# 04_VOLTAGE_CONVERTER.net
KiCad netlist of a schematic drawn in Altium Designer
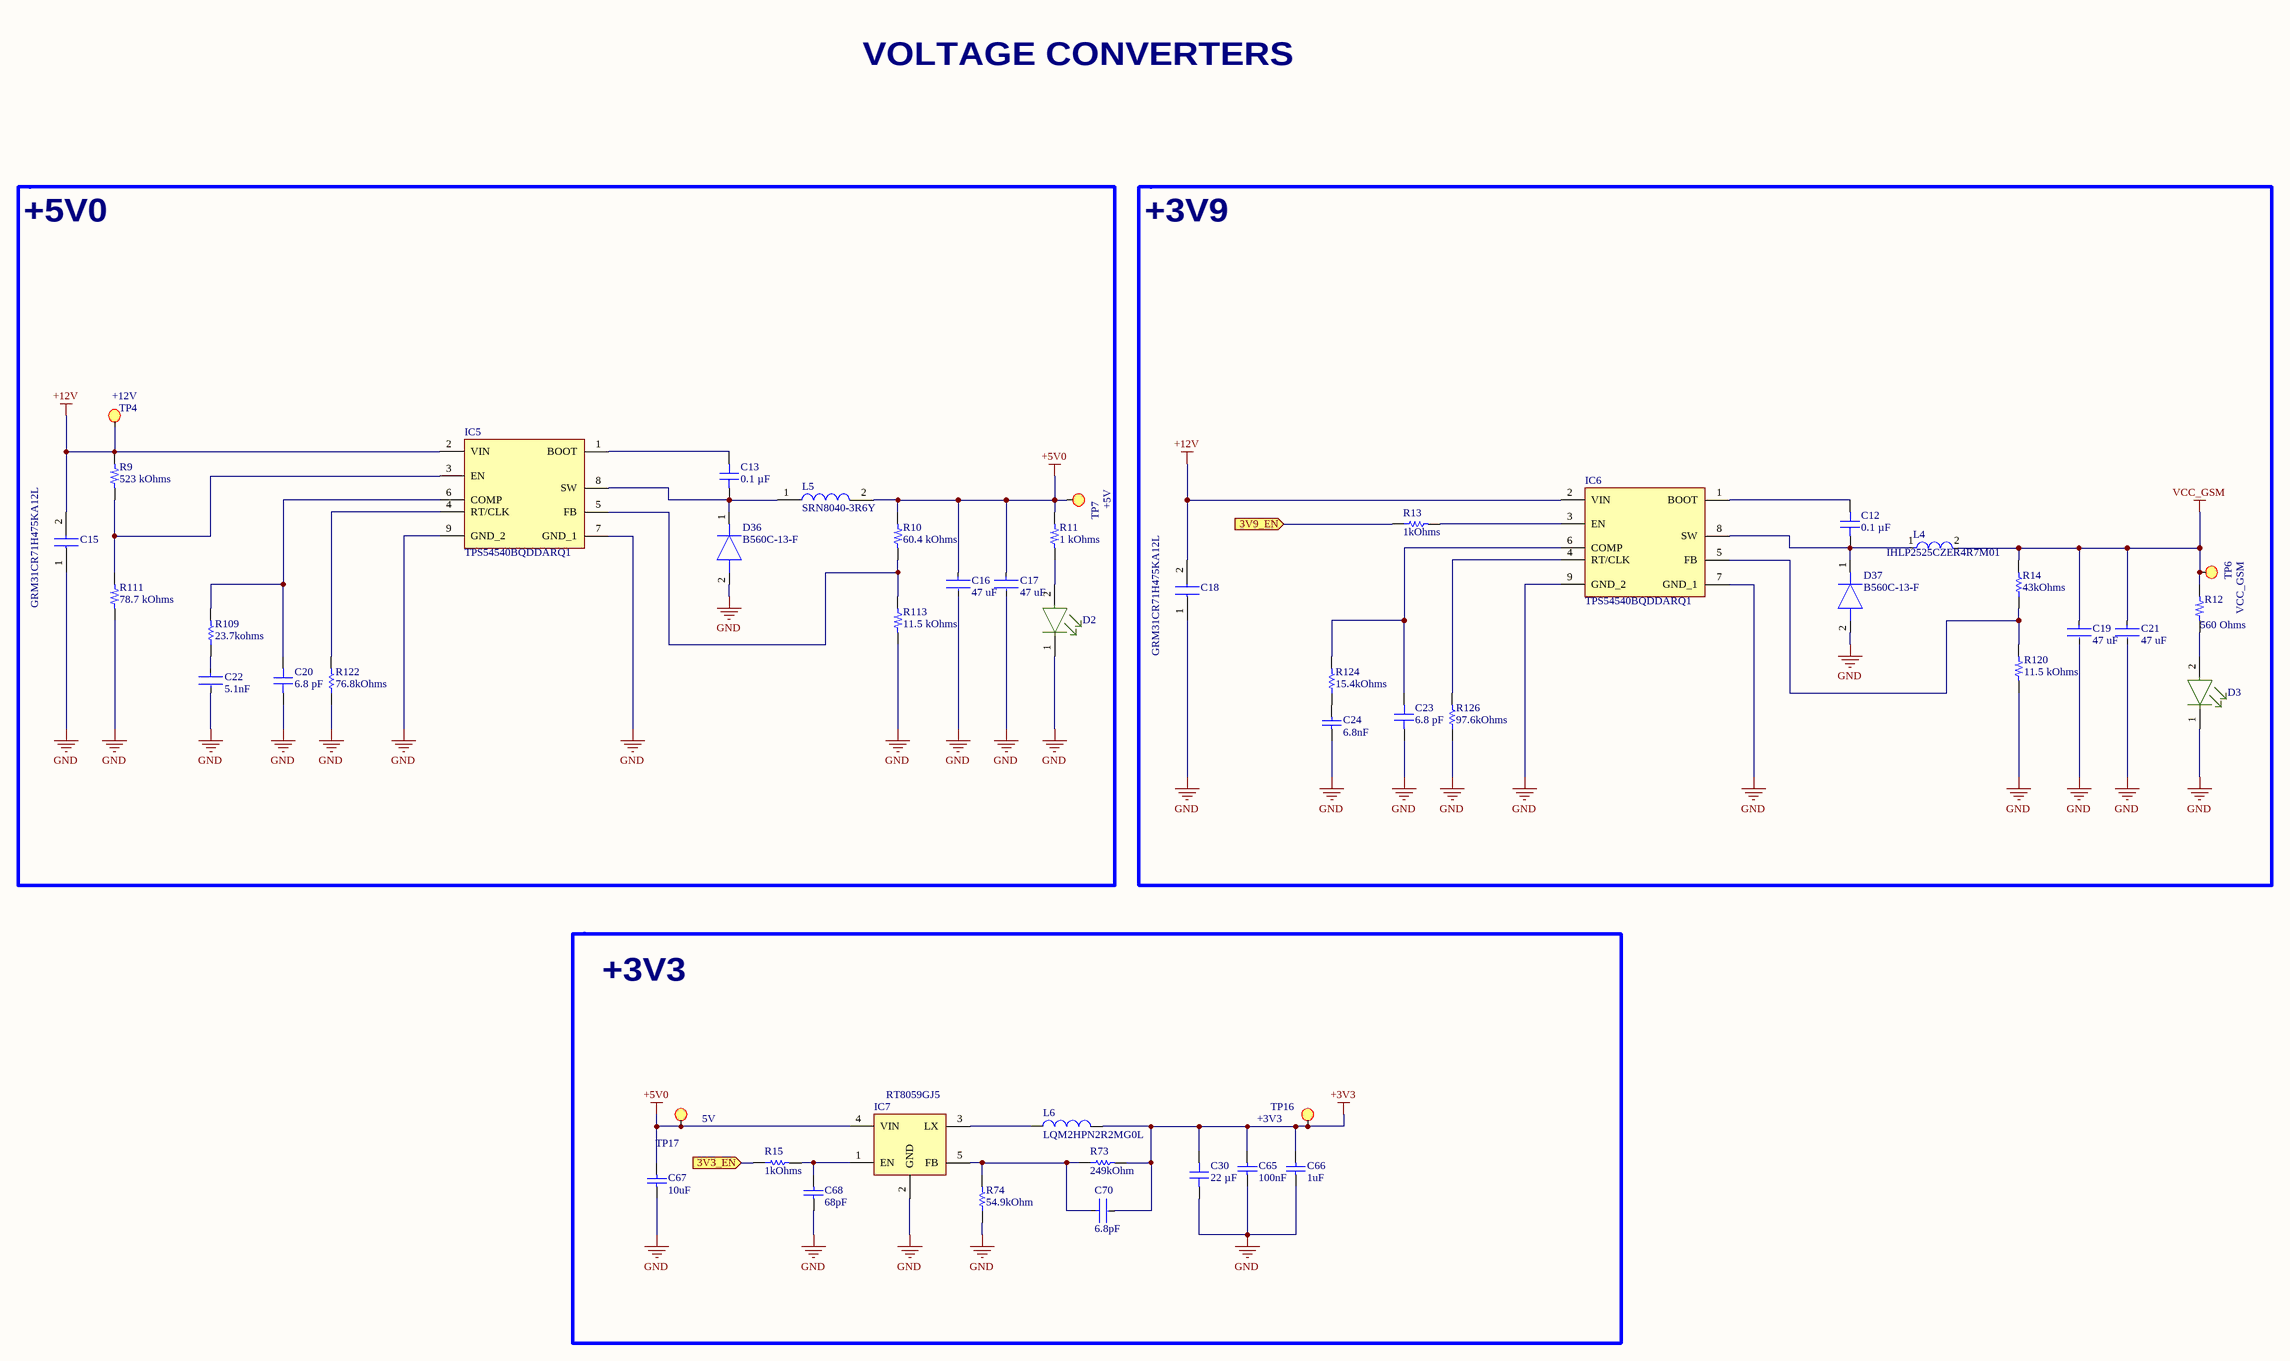
[diagram p0: 04_VOLTAGE_CONVERTER.SchDoc]

(export (version "E")
  (design (tool "Eeschema 10.0.6"))
  (components
    (comp (ref "C12")
      (value "0.1 µF")
      (footprint "CAP0402(1005)X0.5")
      (description "CAP CER 0402 0.1UF 16V X7R 10%")
      (fields (field (name "PART NUMBER") "C0402C104K4RECAUTO") (field (name "MANUFACTURER") "KEMET"))
      (libsource (lib "Celestial Altium Library - altium_library") (part "Capacitor"))
    )
    (comp (ref "C13")
      (value "0.1 µF")
      (footprint "CAP0402(1005)X0.5")
      (description "CAP CER 0402 0.1UF 16V X7R 10%")
      (fields (field (name "PART NUMBER") "C0402C104K4RECAUTO") (field (name "MANUFACTURER") "KEMET"))
      (libsource (lib "Celestial Altium Library - altium_library") (part "Capacitor"))
    )
    (comp (ref "C15")
      (value "GRM31CR71H475KA12L")
      (footprint "CAPC3216X180N")
      (description "Capacitor")
      (fields (field (name "MOUSER PART NUMBER") "81-GRM31CR71H475KA2L"))
      (libsource (lib "HW_HOLLAND_NCDM_MONITOR_R1") (part "GRM31CR71H475KA12L"))
    )
    (comp (ref "C16")
      (value "47 uF")
      (footprint "FP-GRM32E-0_3-0_2-IPC_C")
      (description "CAP CER 47UF 16V X5R 1210")
      (fields (field (name "VOLTAGE") "16V") (field (name "TOLERANCE") "10%"))
      (libsource (lib "Altium Content Vault") (part "b4654b650e69147ec39a6b967a45e02"))
    )
    (comp (ref "C17")
      (value "47 uF")
      (footprint "FP-GRM32E-0_3-0_2-IPC_C")
      (description "CAP CER 47UF 16V X5R 1210")
      (fields (field (name "VOLTAGE") "16V") (field (name "TOLERANCE") "10%"))
      (libsource (lib "Altium Content Vault") (part "b4654b650e69147ec39a6b967a45e02"))
    )
    (comp (ref "C18")
      (value "GRM31CR71H475KA12L")
      (footprint "CAPC3216X180N")
      (description "Capacitor")
      (fields (field (name "MOUSER PART NUMBER") "81-GRM31CR71H475KA2L"))
      (libsource (lib "HW_HOLLAND_NCDM_MONITOR_R1") (part "GRM31CR71H475KA12L"))
    )
    (comp (ref "C19")
      (value "47 uF")
      (footprint "FP-GRM32E-0_3-0_2-IPC_C")
      (description "CAP CER 47UF 16V X5R 1210")
      (fields (field (name "VOLTAGE") "16V") (field (name "TOLERANCE") "10%"))
      (libsource (lib "Altium Content Vault") (part "b4654b650e69147ec39a6b967a45e02"))
    )
    (comp (ref "C20")
      (value "6.8 pF")
      (footprint "CAP0603")
      (description "CAP CER 6.8PF 100V NP0 0603")
      (fields (field (name "PART NUMBER") "06031U6R8BAT2A") (field (name "MANUFACTURER") "KYOCERA AVX"))
      (libsource (lib "Celestial Altium Library - altium_library") (part "Capacitor"))
    )
    (comp (ref "C21")
      (value "47 uF")
      (footprint "FP-GRM32E-0_3-0_2-IPC_C")
      (description "CAP CER 47UF 16V X5R 1210")
      (fields (field (name "VOLTAGE") "16V") (field (name "TOLERANCE") "10%"))
      (libsource (lib "Altium Content Vault") (part "b4654b650e69147ec39a6b967a45e02"))
    )
    (comp (ref "C22")
      (value "5.1nF")
      (footprint "FP-C0603C-CF-MFG")
      (description "CAP CER 5100PF 50V C0G/NP0 0603")
      (fields (field (name "TOLERANCE") "0.05") (field (name "MANUFACTURER") "KEMET"))
      (libsource (lib "Altium Content Vault") (part "b4654b650e69147ec39a6b967a45e02"))
    )
    (comp (ref "C23")
      (value "6.8 pF")
      (footprint "CAP0603")
      (description "CAP CER 6.8PF 100V NP0 0603")
      (fields (field (name "PART NUMBER") "06031U6R8BAT2A") (field (name "MANUFACTURER") "KYOCERA AVX"))
      (libsource (lib "Celestial Altium Library - altium_library") (part "Capacitor"))
    )
    (comp (ref "C24")
      (value "6.8nF")
      (footprint "CAPC1608X90X35NL10T15")
      (fields (field (name "PART NUMBER") "GRM188R72A682KA01D") (field (name "MANUFACTURER") "Murata"))
      (libsource (lib "Altium Content Vault") (part "CAP"))
    )
    (comp (ref "C30")
      (value "22 µF")
      (footprint "CAP1206")
      (description "CAP CER 22UF 25V X5R 1206")
      (fields
        (field (name "PART NUMBER") "CL31A226KAHNNNE")
        (field (name "MANUFACTURER") "Samsung Electro-Mechanics")
      )
      (libsource (lib "Celestial Altium Library - altium_library") (part "Capacitor"))
    )
    (comp (ref "C65")
      (value "100nF")
      (footprint "CAP0603")
      (description "CAP CER 0.1UF 50V X7R 0603")
      (fields (field (name "PART NUMBER") "C0603C104K5RACTU"))
      (libsource (lib "HW_HOLLAND_NCDM_MONITOR_R1") (part "CAP0603_100nF"))
    )
    (comp (ref "C66")
      (value "1uF")
      (footprint "CAP0603")
      (description "CAP CER 1uF 25V X7R 0603")
      (fields (field (name "PART NUMBER") "CGA3E1X7R1E105K080AE"))
      (libsource (lib "HW_HOLLAND_NCDM_MONITOR_R1") (part "CAP0603_100nF"))
    )
    (comp (ref "C67")
      (value "10uF")
      (footprint "CAP0603")
      (description "Ceramic Capacitor,10uF,16V,+/-20%,X5R,0603,Samsung")
      (libsource (lib "HW_HOLLAND_NCDM_MONITOR_R1") (part "CAP0603_100nF"))
    )
    (comp (ref "C68")
      (value "68pF")
      (footprint "CAP0603")
      (description "68 pF ±2% 50V Ceramic Capacitor C0G, NP0 0603 (1608 Metric)")
      (fields (field (name "PART NUMBER") "06035A680GAT2A"))
      (libsource (lib "HW_HOLLAND_NCDM_MONITOR_R1") (part "CAP0603_100nF"))
    )
    (comp (ref "C70")
      (value "6.8pF")
      (footprint "FP-C0603C-CF-MFG")
      (description "CAP CER 6.8PF 50V NP0 0603")
      (fields
        (field (name "MANUFACTURER PART NUMBER") "C0603C689C5GACTU")
        (field (name "OCTOPART") "https://octopart.com/c0603c689c5gactu-kemet-8718591")
      )
      (libsource (lib "Altium Content Vault") (part "b4654b650e69147ec39a6b967a45e02"))
    )
    (comp (ref "D2")
      (value "LED GREEN CLEAR SMD")
      (footprint "Lite-On_GREEN_MFG")
      (description "Green 571nm LED Indication - Discrete 2V 0603 (1608 Metric)")
      (fields (field (name "MANUFACTURER PART NUMBER") "150060VS75000"))
      (libsource (lib "HW_HOLLAND_NCDM_MONITOR_R1") (part "LTST-C191KGKT"))
    )
    (comp (ref "D3")
      (value "LED GREEN CLEAR SMD")
      (footprint "Lite-On_GREEN_MFG")
      (description "Green 571nm LED Indication - Discrete 2V 0603 (1608 Metric)")
      (fields (field (name "MANUFACTURER PART NUMBER") "150060VS75000"))
      (libsource (lib "HW_HOLLAND_NCDM_MONITOR_R1") (part "LTST-C191KGKT"))
    )
    (comp (ref "D36")
      (value "B560C-13-F")
      (footprint "DIOM7959X250N")
      (fields (field (name "MOUSER PART NUMBER") "621-B560C-F"))
      (libsource (lib "HW_HOLLAND_NCDM_MONITOR_R1") (part "B560C-13-F"))
    )
    (comp (ref "D37")
      (value "B560C-13-F")
      (footprint "DIOM7959X250N")
      (fields (field (name "MOUSER PART NUMBER") "621-B560C-F"))
      (libsource (lib "HW_HOLLAND_NCDM_MONITOR_R1") (part "B560C-13-F"))
    )
    (comp (ref "IC5")
      (value "TPS54540BQDDARQ1")
      (footprint "SOIC127P600X170-9N")
      (description "Integrated Circuit")
      (fields (field (name "MOUSER PART NUMBER") "595-TPS54540BQDDARQ1"))
      (libsource (lib "HW_HOLLAND_NCDM_MONITOR_R1") (part "TPS54540BQDDARQ1"))
    )
    (comp (ref "IC6")
      (value "TPS54540BQDDARQ1")
      (footprint "SOIC127P600X170-9N")
      (description "Integrated Circuit")
      (fields (field (name "MOUSER PART NUMBER") "595-TPS54540BQDDARQ1"))
      (libsource (lib "HW_HOLLAND_NCDM_MONITOR_R1") (part "TPS54540BQDDARQ1"))
    )
    (comp (ref "IC7")
      (value "RT8059GJ5")
      (footprint "SOT94P280X100-5N")
      (description "Integrated Circuit")
      (libsource (lib "HW_HOLLAND_NCDM_MONITOR_R1") (part "RT8059GJ5"))
    )
    (comp (ref "L4")
      (value "IHLP2525CZER4R7M01")
      (footprint "FP-IHLP-2525CZ-FP_2_413x3-MFG")
      (description "Commercial Inductors, High Saturation Series 4.7uH 5.5A 40mΩ 20%")
      (fields (field (name "TOLERANCE") "20%"))
      (libsource (lib "Altium Content Vault") (part "725321dda6339637d4d059423bc1c3c"))
    )
    (comp (ref "L5")
      (value "SRN8040-3R6Y")
      (footprint "SRN8040-3R3Y")
      (description "Inductor")
      (libsource (lib "HW_HOLLAND_NCDM_MONITOR_R1") (part "SRN8040-3R3Y"))
    )
    (comp (ref "L6")
      (value "LQM2HPN2R2MG0L")
      (footprint "INDC2520X100N")
      (description "Inductor Power Chip Shielded Multi-Layer 2.2uH 20% 1MHz Ferrite 1.3A 100mOhm DCR 1008 T/R")
      (libsource (lib "HW_HOLLAND_NCDM_MONITOR_R1") (part "LQM2HPN2R2MG0L"))
    )
    (comp (ref "R9")
      (value "523 kOhms")
      (footprint "RES0402(1005)")
      (description "RES SMD 523K OHM 1% 1/16W 0402")
      (fields (field (name "PART NUMBER") "CRCW0402523KFKED") (field (name "MANUFACTURER") "Vishay Dale"))
      (libsource (lib "Celestial Altium Library - altium_library") (part "Resistor"))
    )
    (comp (ref "R10")
      (value "60.4 kOhms")
      (footprint "RES0402(1005)")
      (description "RES SMD 60.4K OHM 1% 1/16W 0402")
      (fields (field (name "PART NUMBER") "CRCW040260K4FKED") (field (name "MANUFACTURER") "Vishay Dale"))
      (libsource (lib "Celestial Altium Library - altium_library") (part "Resistor"))
    )
    (comp (ref "R11")
      (value "1 kOhms")
      (footprint "RES 0603_1608")
      (description "RES 1K OHM 1% 1/8W 0603")
      (fields
        (field (name "PART NUMBER") "RNCP0603FTD1K00")
        (field (name "MANUFACTURER") "Stackpole Electronics Inc")
      )
      (libsource (lib "Celestial Altium Library - altium_library") (part "Resistor"))
    )
    (comp (ref "R12")
      (value "560 Ohms")
      (footprint "RES 0402_1005")
      (description "ANTI-SURGE CHIP RESISTORS")
      (fields (field (name "PART NUMBER") "ESR01MZPF5600"))
      (libsource (lib "Celestial Altium Library - altium_library") (part "Resistor"))
    )
    (comp (ref "R13")
      (value "1kOhms")
      (footprint "RESC1005X40X25LL05T10")
      (fields (field (name "PART NUMBER") "CRCW04021K00FKEDHP") (field (name "MANUFACTURER") "Vishay Dale"))
      (libsource (lib "Altium Content Vault") (part "RES"))
    )
    (comp (ref "R14")
      (value "43kOhms")
      (footprint "RESC1005X40X25NL05T05")
      (fields (field (name "PART NUMBER") "CRCW040243K0FKED") (field (name "MANUFACTURER") "Vishay Dale"))
      (libsource (lib "Altium Content Vault") (part "RES"))
    )
    (comp (ref "R15")
      (value "1kOhms")
      (footprint "RESC1005X40X25LL05T10")
      (fields (field (name "PART NUMBER") "CRCW04021K00FKEDHP") (field (name "MANUFACTURER") "Vishay Dale"))
      (libsource (lib "Altium Content Vault") (part "RES"))
    )
    (comp (ref "R73")
      (value "249kOhm")
      (footprint "RESC1005X40X25NL05T05")
      (fields (field (name "PART NUMBER") "CRCW0402249KFKED") (field (name "MANUFACTURER") "Vishay Dale"))
      (libsource (lib "Altium Content Vault") (part "RES"))
    )
    (comp (ref "R74")
      (value "54.9kOhm")
      (footprint "RESC1005X40X25LL05T10")
      (fields (field (name "PART NUMBER") "RC0402FR-0754K9L") (field (name "MANUFACTURER") "Yageo / Phycomp"))
      (libsource (lib "Altium Content Vault") (part "RES"))
    )
    (comp (ref "R109")
      (value "23.7kohms")
      (footprint "RESC1005X40X25ML05T05")
      (description "RES SMD 23.7K OHM 1% 1/16W 0402")
      (fields (field (name "PART NUMBER") "CRCW040223K7FKED") (field (name "MANUFACTURER") "Vishay Dale"))
      (libsource (lib "Altium Content Vault") (part "RES"))
    )
    (comp (ref "R111")
      (value "78.7 kOhms")
      (footprint "RES0402(1005)")
      (description "RES SMD 78.7K OHM 1% 1/16W 0402")
      (fields (field (name "PART NUMBER") "CRCW040278K7FKED") (field (name "TOLERANCE") "±1%"))
      (libsource (lib "Celestial Altium Library - altium_library") (part "Resistor"))
    )
    (comp (ref "R113")
      (value "11.5 kOhms")
      (footprint "RES0402(1005)")
      (description "RES SMD 11.5K OHM 1% 1/16W 0402")
      (fields (field (name "PART NUMBER") "CRCW040211K5FKED") (field (name "MANUFACTURER") "Vishay Dale"))
      (libsource (lib "Celestial Altium Library - altium_library") (part "Resistor"))
    )
    (comp (ref "R120")
      (value "11.5 kOhms")
      (footprint "RES0402(1005)")
      (description "RES SMD 11.5K OHM 1% 1/16W 0402")
      (fields (field (name "PART NUMBER") "CRCW040211K5FKED") (field (name "MANUFACTURER") "Vishay Dale"))
      (libsource (lib "Celestial Altium Library - altium_library") (part "Resistor"))
    )
    (comp (ref "R122")
      (value "76.8kOhms")
      (footprint "RESC1609X50X30ML10T20")
      (fields (field (name "PART NUMBER") "CRCW060376K8FKEA") (field (name "MANUFACTURER") "Vishay Dale"))
      (libsource (lib "Altium Content Vault") (part "RES"))
    )
    (comp (ref "R124")
      (value "15.4kOhms")
      (footprint "RESC1005X40X25ML05T05")
      (fields (field (name "MANUFACTURER") "Vishay Dale") (field (name "PART NUMBER") "CRCW040215K4FKED"))
      (libsource (lib "Altium Content Vault") (part "RES"))
    )
    (comp (ref "R126")
      (value "97.6kOhms")
      (footprint "RESC1005X40X25ML05T10")
      (fields (field (name "MANUFACTURER") "Yageo") (field (name "PART NUMBER") "RC0402FR-0797K6L"))
      (libsource (lib "Altium Content Vault") (part "RES"))
    )
    (comp (ref "TP4")
      (value "+12V")
      (footprint "TEST_POINT_SMD")
      (libsource (lib "HW_HOLLAND_NCDM_MONITOR_R1") (part "TP"))
    )
    (comp (ref "TP6")
      (value "VCC_GSM")
      (footprint "TEST_POINT_SMD")
      (libsource (lib "HW_HOLLAND_NCDM_MONITOR_R1") (part "TP"))
    )
    (comp (ref "TP7")
      (value "+5V")
      (footprint "TEST_POINT_SMD")
      (libsource (lib "HW_HOLLAND_NCDM_MONITOR_R1") (part "TP"))
    )
    (comp (ref "TP16")
      (value "+3V3")
      (footprint "TEST_POINT_SMD")
      (libsource (lib "HW_HOLLAND_NCDM_MONITOR_R1") (part "TP"))
    )
    (comp (ref "TP17")
      (value "5V")
      (footprint "TEST_POINT_SMD")
      (libsource (lib "HW_HOLLAND_NCDM_MONITOR_R1") (part "TP"))
    )
  )
  (nets
    (net (code "1") (name "+3V3") (class "Default")
      (node (ref "C30") (pin "2") (pinfunction "2_2") (pintype "passive"))
      (node (ref "C65") (pin "2") (pinfunction "2_2") (pintype "passive"))
      (node (ref "C66") (pin "2") (pinfunction "2_2") (pintype "passive"))
      (node (ref "C70") (pin "2") (pinfunction "2_2") (pintype "passive"))
      (node (ref "L6") (pin "2") (pinfunction "2_2") (pintype "passive"))
      (node (ref "R73") (pin "2") (pinfunction "2_2") (pintype "passive"))
      (node (ref "TP16") (pin "1") (pinfunction "TP_1") (pintype "passive"))
    )
    (net (code "2") (name "+5V0") (class "Default")
      (node (ref "C16") (pin "1") (pinfunction "1_1") (pintype "passive"))
      (node (ref "C17") (pin "1") (pinfunction "1_1") (pintype "passive"))
      (node (ref "C67") (pin "1") (pinfunction "1_1") (pintype "passive"))
      (node (ref "IC7") (pin "4") (pinfunction "VIN_4") (pintype "passive"))
      (node (ref "L5") (pin "2") (pinfunction "2_2") (pintype "passive"))
      (node (ref "R10") (pin "2") (pinfunction "2_2") (pintype "passive"))
      (node (ref "R11") (pin "2") (pinfunction "2_2") (pintype "passive"))
      (node (ref "TP17") (pin "1") (pinfunction "TP_1") (pintype "passive"))
      (node (ref "TP7") (pin "1") (pinfunction "TP_1") (pintype "passive"))
    )
    (net (code "3") (name "+12V") (class "Default")
      (node (ref "C15") (pin "2") (pinfunction "2_2") (pintype "passive"))
      (node (ref "C18") (pin "2") (pinfunction "2_2") (pintype "passive"))
      (node (ref "IC5") (pin "2") (pinfunction "VIN_2") (pintype "passive"))
      (node (ref "IC6") (pin "2") (pinfunction "VIN_2") (pintype "passive"))
      (node (ref "R9") (pin "2") (pinfunction "2_2") (pintype "passive"))
      (node (ref "TP4") (pin "1") (pinfunction "TP_1") (pintype "passive"))
    )
    (net (code "4") (name "/3V3_EN") (class "Default")
      (node (ref "R15") (pin "1") (pinfunction "1_1") (pintype "passive"))
    )
    (net (code "5") (name "/3V9_EN") (class "Default")
      (node (ref "R13") (pin "1") (pinfunction "1_1") (pintype "passive"))
    )
    (net (code "6") (name "GND") (class "Default")
      (node (ref "C15") (pin "1") (pinfunction "1_1") (pintype "passive"))
      (node (ref "C16") (pin "2") (pinfunction "2_2") (pintype "passive"))
      (node (ref "C17") (pin "2") (pinfunction "2_2") (pintype "passive"))
      (node (ref "C18") (pin "1") (pinfunction "1_1") (pintype "passive"))
      (node (ref "C19") (pin "2") (pinfunction "2_2") (pintype "passive"))
      (node (ref "C20") (pin "1") (pinfunction "1_1") (pintype "passive"))
      (node (ref "C21") (pin "2") (pinfunction "2_2") (pintype "passive"))
      (node (ref "C22") (pin "2") (pinfunction "2_2") (pintype "passive"))
      (node (ref "C23") (pin "1") (pinfunction "1_1") (pintype "passive"))
      (node (ref "C24") (pin "1") (pinfunction "1_1") (pintype "passive"))
      (node (ref "C30") (pin "1") (pinfunction "1_1") (pintype "passive"))
      (node (ref "C65") (pin "1") (pinfunction "1_1") (pintype "passive"))
      (node (ref "C66") (pin "1") (pinfunction "1_1") (pintype "passive"))
      (node (ref "C67") (pin "2") (pinfunction "2_2") (pintype "passive"))
      (node (ref "C68") (pin "2") (pinfunction "2_2") (pintype "passive"))
      (node (ref "D2") (pin "1") (pinfunction "C_1") (pintype "passive"))
      (node (ref "D3") (pin "1") (pinfunction "C_1") (pintype "passive"))
      (node (ref "D36") (pin "2") (pinfunction "A_2") (pintype "passive"))
      (node (ref "D37") (pin "2") (pinfunction "A_2") (pintype "passive"))
      (node (ref "IC5") (pin "7") (pinfunction "GND_1_7") (pintype "passive"))
      (node (ref "IC5") (pin "9") (pinfunction "GND_2_9") (pintype "passive"))
      (node (ref "IC6") (pin "7") (pinfunction "GND_1_7") (pintype "passive"))
      (node (ref "IC6") (pin "9") (pinfunction "GND_2_9") (pintype "passive"))
      (node (ref "IC7") (pin "2") (pinfunction "GND_2") (pintype "passive"))
      (node (ref "R111") (pin "1") (pinfunction "1_1") (pintype "passive"))
      (node (ref "R113") (pin "1") (pinfunction "1_1") (pintype "passive"))
      (node (ref "R120") (pin "1") (pinfunction "1_1") (pintype "passive"))
      (node (ref "R122") (pin "1") (pinfunction "1_1") (pintype "passive"))
      (node (ref "R126") (pin "1") (pinfunction "1_1") (pintype "passive"))
      (node (ref "R74") (pin "1") (pinfunction "1_1") (pintype "passive"))
    )
    (net (code "7") (name "Net-(C22-Pad1)") (class "Default")
      (node (ref "C22") (pin "1") (pinfunction "1_1") (pintype "passive"))
      (node (ref "R109") (pin "1") (pinfunction "1_1") (pintype "passive"))
    )
    (net (code "8") (name "Net-(C24-Pad2)") (class "Default")
      (node (ref "C24") (pin "2") (pinfunction "2_2") (pintype "passive"))
      (node (ref "R124") (pin "1") (pinfunction "1_1") (pintype "passive"))
    )
    (net (code "9") (name "Net-(D2-A)") (class "Default")
      (node (ref "D2") (pin "2") (pinfunction "A_2") (pintype "passive"))
      (node (ref "R11") (pin "1") (pinfunction "1_1") (pintype "passive"))
    )
    (net (code "10") (name "Net-(D3-A)") (class "Default")
      (node (ref "D3") (pin "2") (pinfunction "A_2") (pintype "passive"))
      (node (ref "R12") (pin "1") (pinfunction "1_1") (pintype "passive"))
    )
    (net (code "11") (name "Net-(D36-K)") (class "Default")
      (node (ref "C13") (pin "1") (pinfunction "1_1") (pintype "passive"))
      (node (ref "D36") (pin "1") (pinfunction "K_1") (pintype "passive"))
      (node (ref "IC5") (pin "8") (pinfunction "SW_8") (pintype "passive"))
      (node (ref "L5") (pin "1") (pinfunction "1_1") (pintype "passive"))
    )
    (net (code "12") (name "Net-(D37-K)") (class "Default")
      (node (ref "C12") (pin "1") (pinfunction "1_1") (pintype "passive"))
      (node (ref "D37") (pin "1") (pinfunction "K_1") (pintype "passive"))
      (node (ref "IC6") (pin "8") (pinfunction "SW_8") (pintype "passive"))
      (node (ref "L4") (pin "1") (pinfunction "1_1") (pintype "passive"))
    )
    (net (code "13") (name "Net-(IC5-BOOT)") (class "Default")
      (node (ref "C13") (pin "2") (pinfunction "2_2") (pintype "passive"))
      (node (ref "IC5") (pin "1") (pinfunction "BOOT_1") (pintype "passive"))
    )
    (net (code "14") (name "Net-(IC5-COMP)") (class "Default")
      (node (ref "C20") (pin "2") (pinfunction "2_2") (pintype "passive"))
      (node (ref "IC5") (pin "6") (pinfunction "COMP_6") (pintype "passive"))
      (node (ref "R109") (pin "2") (pinfunction "2_2") (pintype "passive"))
    )
    (net (code "15") (name "Net-(IC5-EN)") (class "Default")
      (node (ref "IC5") (pin "3") (pinfunction "EN_3") (pintype "passive"))
      (node (ref "R111") (pin "2") (pinfunction "2_2") (pintype "passive"))
      (node (ref "R9") (pin "1") (pinfunction "1_1") (pintype "passive"))
    )
    (net (code "16") (name "Net-(IC5-FB)") (class "Default")
      (node (ref "IC5") (pin "5") (pinfunction "FB_5") (pintype "passive"))
      (node (ref "R10") (pin "1") (pinfunction "1_1") (pintype "passive"))
      (node (ref "R113") (pin "2") (pinfunction "2_2") (pintype "passive"))
    )
    (net (code "17") (name "Net-(IC5-RT{slash}CLK)") (class "Default")
      (node (ref "IC5") (pin "4") (pinfunction "RT/CLK_4") (pintype "passive"))
      (node (ref "R122") (pin "2") (pinfunction "2_2") (pintype "passive"))
    )
    (net (code "18") (name "Net-(IC6-BOOT)") (class "Default")
      (node (ref "C12") (pin "2") (pinfunction "2_2") (pintype "passive"))
      (node (ref "IC6") (pin "1") (pinfunction "BOOT_1") (pintype "passive"))
    )
    (net (code "19") (name "Net-(IC6-COMP)") (class "Default")
      (node (ref "C23") (pin "2") (pinfunction "2_2") (pintype "passive"))
      (node (ref "IC6") (pin "6") (pinfunction "COMP_6") (pintype "passive"))
      (node (ref "R124") (pin "2") (pinfunction "2_2") (pintype "passive"))
    )
    (net (code "20") (name "Net-(IC6-EN)") (class "Default")
      (node (ref "IC6") (pin "3") (pinfunction "EN_3") (pintype "passive"))
      (node (ref "R13") (pin "2") (pinfunction "2_2") (pintype "passive"))
    )
    (net (code "21") (name "Net-(IC6-FB)") (class "Default")
      (node (ref "IC6") (pin "5") (pinfunction "FB_5") (pintype "passive"))
      (node (ref "R120") (pin "2") (pinfunction "2_2") (pintype "passive"))
      (node (ref "R14") (pin "1") (pinfunction "1_1") (pintype "passive"))
    )
    (net (code "22") (name "Net-(IC6-RT{slash}CLK)") (class "Default")
      (node (ref "IC6") (pin "4") (pinfunction "RT/CLK_4") (pintype "passive"))
      (node (ref "R126") (pin "2") (pinfunction "2_2") (pintype "passive"))
    )
    (net (code "23") (name "Net-(IC7-EN)") (class "Default")
      (node (ref "C68") (pin "1") (pinfunction "1_1") (pintype "passive"))
      (node (ref "IC7") (pin "1") (pinfunction "EN_1") (pintype "passive"))
      (node (ref "R15") (pin "2") (pinfunction "2_2") (pintype "passive"))
    )
    (net (code "24") (name "Net-(IC7-FB)") (class "Default")
      (node (ref "C70") (pin "1") (pinfunction "1_1") (pintype "passive"))
      (node (ref "IC7") (pin "5") (pinfunction "FB_5") (pintype "passive"))
      (node (ref "R73") (pin "1") (pinfunction "1_1") (pintype "passive"))
      (node (ref "R74") (pin "2") (pinfunction "2_2") (pintype "passive"))
    )
    (net (code "25") (name "Net-(IC7-LX)") (class "Default")
      (node (ref "IC7") (pin "3") (pinfunction "LX_3") (pintype "passive"))
      (node (ref "L6") (pin "1") (pinfunction "1_1") (pintype "passive"))
    )
    (net (code "26") (name "VCC_GSM") (class "Default")
      (node (ref "C19") (pin "1") (pinfunction "1_1") (pintype "passive"))
      (node (ref "C21") (pin "1") (pinfunction "1_1") (pintype "passive"))
      (node (ref "L4") (pin "2") (pinfunction "2_2") (pintype "passive"))
      (node (ref "R12") (pin "2") (pinfunction "2_2") (pintype "passive"))
      (node (ref "R14") (pin "2") (pinfunction "2_2") (pintype "passive"))
      (node (ref "TP6") (pin "1") (pinfunction "TP_1") (pintype "passive"))
    )
  )
)
